# Sensor00.net
KiCad netlist of a schematic drawn in Altium Designer
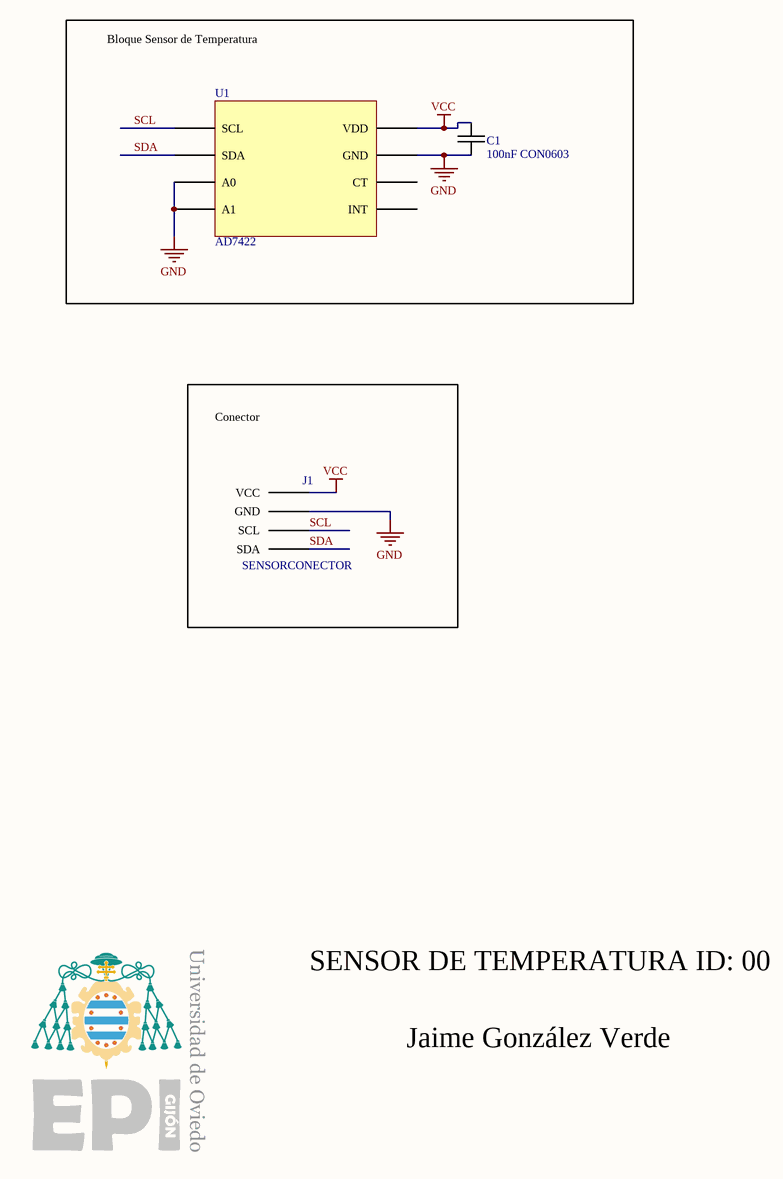
[diagram p0: Sensor00.SchDoc]

(export (version "E")
  (design (tool "Eeschema 10.0.6"))
  (components
    (comp (ref "C1")
      (value "100nF CON0603")
      (footprint "CAPC0603X06N")
      (libsource (lib "JaimeGlez") (part "CON0603"))
    )
    (comp (ref "J1")
      (value "SENSORCONECTOR")
      (footprint "ConectorSMD1,3mm")
      (libsource (lib "JaimeGlez") (part "SENSORCONECTOR"))
    )
    (comp (ref "U1") (value "AD7422") (footprint "ADT7422") (libsource (lib "JaimeGlez") (part "AD7422")))
  )
  (nets
    (net (code "1") (name "/SCL") (class "Default")
      (node (ref "J1") (pin "1") (pinfunction "SCL_1") (pintype "passive"))
      (node (ref "U1") (pin "1") (pinfunction "SCL_1") (pintype "passive"))
    )
    (net (code "2") (name "/SDA") (class "Default")
      (node (ref "J1") (pin "0") (pinfunction "SDA_0") (pintype "passive"))
      (node (ref "U1") (pin "2") (pinfunction "SDA_2") (pintype "passive"))
    )
    (net (code "3") (name "GND") (class "Default")
      (node (ref "C1") (pin "2") (pintype "passive"))
      (node (ref "J1") (pin "2") (pinfunction "GND_2") (pintype "passive"))
      (node (ref "U1") (pin "11") (pinfunction "GND_11") (pintype "passive"))
      (node (ref "U1") (pin "3") (pinfunction "A0_3") (pintype "passive"))
      (node (ref "U1") (pin "4") (pinfunction "A1_4") (pintype "passive"))
    )
    (net (code "4") (name "VCC") (class "Default")
      (node (ref "C1") (pin "1") (pintype "passive"))
      (node (ref "J1") (pin "3") (pinfunction "VCC_3") (pintype "passive"))
      (node (ref "U1") (pin "12") (pinfunction "VDD_12") (pintype "passive"))
    )
    (net (code "5") (name "unconnected-(U1-CT-Pad10)") (class "Default")
      (node (ref "U1") (pin "10") (pinfunction "CT_10") (pintype "passive"))
    )
    (net (code "6") (name "unconnected-(U1-INT-Pad9)") (class "Default")
      (node (ref "U1") (pin "9") (pinfunction "INT_9") (pintype "passive"))
    )
  )
)
